# 04_POWER_LDO.net
KiCad netlist of a schematic drawn in Altium Designer
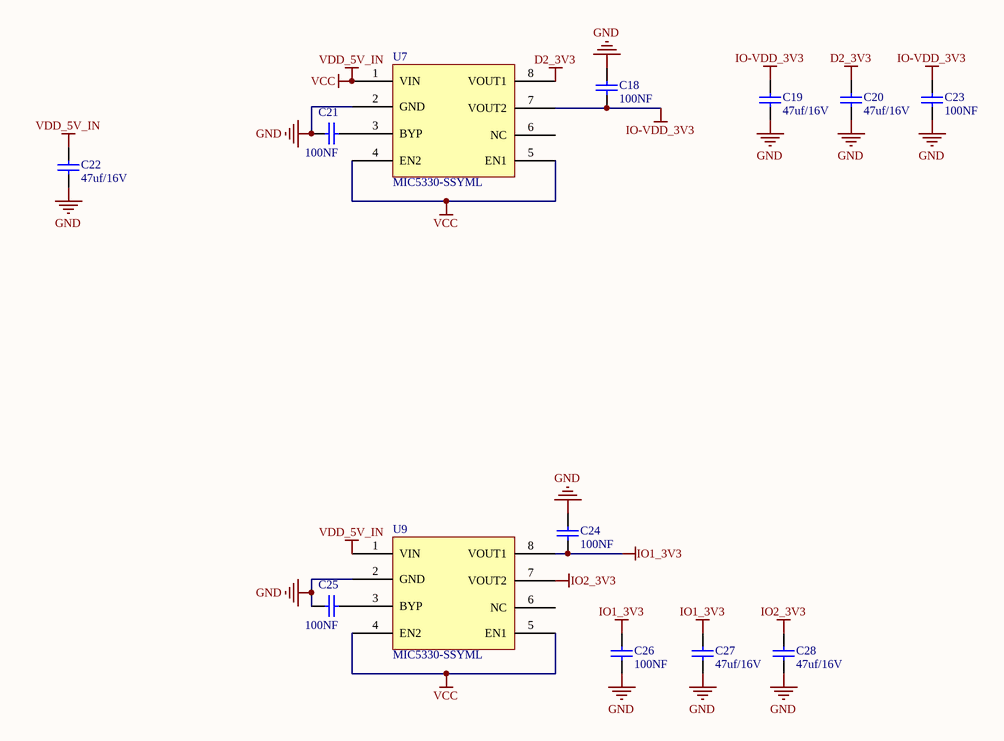
[diagram p0: 04_POWER_LDO.SchDoc]

(export (version "E")
  (design (tool "Eeschema 10.0.6"))
  (components
    (comp (ref "C18")
      (value "100NF")
      (fields (field (name "PUBLISHER") "Altium Limited"))
      (libsource (lib "Miscellaneous Devices") (part "Cap"))
    )
    (comp (ref "C19")
      (value "47uf/16V")
      (description "Capacitor")
      (libsource (lib "Miscellaneous Devices") (part "Cap"))
    )
    (comp (ref "C20")
      (value "47uf/16V")
      (description "Capacitor")
      (libsource (lib "Miscellaneous Devices") (part "Cap"))
    )
    (comp (ref "C21")
      (value "100NF")
      (fields (field (name "PUBLISHER") "Altium Limited"))
      (libsource (lib "Miscellaneous Devices") (part "Cap"))
    )
    (comp (ref "C22")
      (value "47uf/16V")
      (description "Capacitor")
      (libsource (lib "Miscellaneous Devices") (part "Cap"))
    )
    (comp (ref "C23") (value "100NF") (libsource (lib "Miscellaneous Devices") (part "Cap")))
    (comp (ref "C24")
      (value "100NF")
      (fields (field (name "PUBLISHER") "Altium Limited"))
      (libsource (lib "Miscellaneous Devices") (part "Cap"))
    )
    (comp (ref "C25")
      (value "100NF")
      (fields (field (name "PUBLISHER") "Altium Limited"))
      (libsource (lib "Miscellaneous Devices") (part "Cap"))
    )
    (comp (ref "C26") (value "100NF") (libsource (lib "Miscellaneous Devices") (part "Cap")))
    (comp (ref "C27")
      (value "47uf/16V")
      (description "Capacitor")
      (libsource (lib "Miscellaneous Devices") (part "Cap"))
    )
    (comp (ref "C28")
      (value "47uf/16V")
      (description "Capacitor")
      (libsource (lib "Miscellaneous Devices") (part "Cap"))
    )
    (comp (ref "U7") (value "MIC5330-SSYML") (footprint "MIC5530") (libsource (lib "hack") (part "MIC5530")))
    (comp (ref "U9") (value "MIC5330-SSYML") (footprint "MIC5530") (libsource (lib "hack") (part "MIC5530")))
  )
  (nets
    (net (code "1") (name "D2_3V3") (class "Default")
      (node (ref "C20") (pin "1") (pinfunction "1_1") (pintype "passive"))
      (node (ref "U7") (pin "8") (pinfunction "VOUT1_8") (pintype "passive"))
    )
    (net (code "2") (name "GND") (class "Default")
      (node (ref "C18") (pin "2") (pinfunction "2_2") (pintype "passive"))
      (node (ref "C19") (pin "2") (pinfunction "2_2") (pintype "passive"))
      (node (ref "C20") (pin "2") (pinfunction "2_2") (pintype "passive"))
      (node (ref "C21") (pin "2") (pinfunction "2_2") (pintype "passive"))
      (node (ref "C22") (pin "2") (pinfunction "2_2") (pintype "passive"))
      (node (ref "C23") (pin "1") (pinfunction "1_1") (pintype "passive"))
      (node (ref "C24") (pin "2") (pinfunction "2_2") (pintype "passive"))
      (node (ref "C25") (pin "2") (pinfunction "2_2") (pintype "passive"))
      (node (ref "C26") (pin "1") (pinfunction "1_1") (pintype "passive"))
      (node (ref "C27") (pin "2") (pinfunction "2_2") (pintype "passive"))
      (node (ref "C28") (pin "2") (pinfunction "2_2") (pintype "passive"))
      (node (ref "U7") (pin "2") (pinfunction "GND_2") (pintype "passive"))
      (node (ref "U9") (pin "2") (pinfunction "GND_2") (pintype "passive"))
    )
    (net (code "3") (name "IO-VDD_3V3") (class "Default")
      (node (ref "C18") (pin "1") (pinfunction "1_1") (pintype "passive"))
      (node (ref "C19") (pin "1") (pinfunction "1_1") (pintype "passive"))
      (node (ref "C23") (pin "2") (pinfunction "2_2") (pintype "passive"))
      (node (ref "U7") (pin "7") (pinfunction "VOUT2_7") (pintype "passive"))
    )
    (net (code "4") (name "IO1_3V3") (class "Default")
      (node (ref "C24") (pin "1") (pinfunction "1_1") (pintype "passive"))
      (node (ref "C26") (pin "2") (pinfunction "2_2") (pintype "passive"))
      (node (ref "C27") (pin "1") (pinfunction "1_1") (pintype "passive"))
      (node (ref "U9") (pin "8") (pinfunction "VOUT1_8") (pintype "passive"))
    )
    (net (code "5") (name "IO2_3V3") (class "Default")
      (node (ref "C28") (pin "1") (pinfunction "1_1") (pintype "passive"))
      (node (ref "U9") (pin "7") (pinfunction "VOUT2_7") (pintype "passive"))
    )
    (net (code "6") (name "Net-(U7-BYP)") (class "Default")
      (node (ref "C21") (pin "1") (pinfunction "1_1") (pintype "passive"))
      (node (ref "U7") (pin "3") (pinfunction "BYP_3") (pintype "passive"))
    )
    (net (code "7") (name "Net-(U9-BYP)") (class "Default")
      (node (ref "C25") (pin "1") (pinfunction "1_1") (pintype "passive"))
      (node (ref "U9") (pin "3") (pinfunction "BYP_3") (pintype "passive"))
    )
    (net (code "8") (name "VCC") (class "Default")
      (node (ref "C22") (pin "1") (pinfunction "1_1") (pintype "passive"))
      (node (ref "U7") (pin "1") (pinfunction "VIN_1") (pintype "passive"))
      (node (ref "U7") (pin "4") (pinfunction "EN2_4") (pintype "passive"))
      (node (ref "U7") (pin "5") (pinfunction "EN1_5") (pintype "passive"))
      (node (ref "U9") (pin "1") (pinfunction "VIN_1") (pintype "passive"))
      (node (ref "U9") (pin "4") (pinfunction "EN2_4") (pintype "passive"))
      (node (ref "U9") (pin "5") (pinfunction "EN1_5") (pintype "passive"))
    )
    (net (code "9") (name "unconnected-(U7-NC-Pad6)") (class "Default")
      (node (ref "U7") (pin "6") (pinfunction "NC_6") (pintype "passive"))
    )
    (net (code "10") (name "unconnected-(U9-NC-Pad6)") (class "Default")
      (node (ref "U9") (pin "6") (pinfunction "NC_6") (pintype "passive"))
    )
  )
)
